# Buttons.net
KiCad netlist of a schematic drawn in Altium Designer
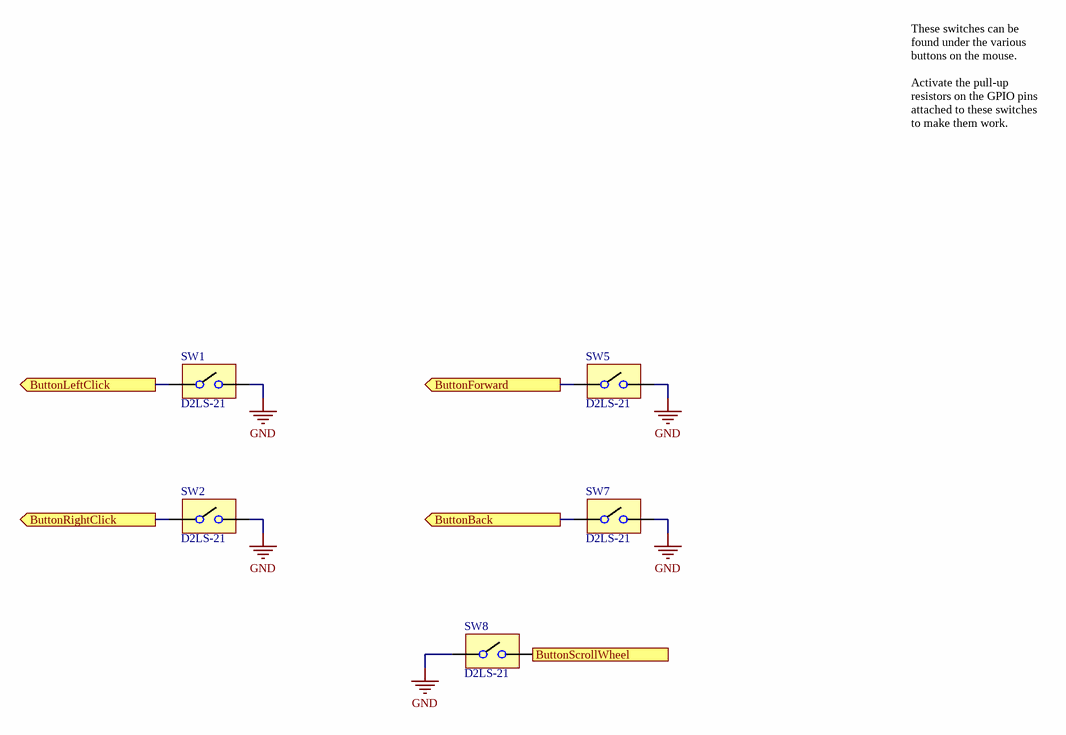
[diagram p0: Buttons.SchDoc]

(export (version "E")
  (design (tool "Eeschema 10.0.6"))
  (components
    (comp (ref "SW1")
      (value "D2LS-21")
      (footprint "D2LS-21")
      (description "Compact Surface-mounting Switch for long durability")
      (libsource (lib "Switches") (part "D2LS-21"))
    )
    (comp (ref "SW2")
      (value "D2LS-21")
      (footprint "D2LS-21")
      (description "Compact Surface-mounting Switch for long durability")
      (libsource (lib "Switches") (part "D2LS-21"))
    )
    (comp (ref "SW5")
      (value "D2LS-21")
      (footprint "D2LS-21")
      (description "Compact Surface-mounting Switch for long durability")
      (libsource (lib "Switches") (part "D2LS-21"))
    )
    (comp (ref "SW7")
      (value "D2LS-21")
      (footprint "D2LS-21")
      (description "Compact Surface-mounting Switch for long durability")
      (libsource (lib "Switches") (part "D2LS-21"))
    )
    (comp (ref "SW8")
      (value "D2LS-21")
      (footprint "D2LS-21")
      (description "Compact Surface-mounting Switch for long durability")
      (libsource (lib "Switches") (part "D2LS-21"))
    )
  )
  (nets
    (net (code "1") (name "/ButtonBack") (class "Default")
      (node (ref "SW7") (pin "A") (pinfunction "A_A") (pintype "passive"))
    )
    (net (code "2") (name "/ButtonForward") (class "Default")
      (node (ref "SW5") (pin "A") (pinfunction "A_A") (pintype "passive"))
    )
    (net (code "3") (name "/ButtonLeftClick") (class "Default")
      (node (ref "SW1") (pin "A") (pinfunction "A_A") (pintype "passive"))
    )
    (net (code "4") (name "/ButtonRightClick") (class "Default")
      (node (ref "SW2") (pin "A") (pinfunction "A_A") (pintype "passive"))
    )
    (net (code "5") (name "/ButtonScrollWheel") (class "Default")
      (node (ref "SW8") (pin "B") (pinfunction "B_B") (pintype "passive"))
    )
    (net (code "6") (name "GND") (class "Default")
      (node (ref "SW1") (pin "B") (pinfunction "B_B") (pintype "passive"))
      (node (ref "SW2") (pin "B") (pinfunction "B_B") (pintype "passive"))
      (node (ref "SW5") (pin "B") (pinfunction "B_B") (pintype "passive"))
      (node (ref "SW7") (pin "B") (pinfunction "B_B") (pintype "passive"))
      (node (ref "SW8") (pin "A") (pinfunction "A_A") (pintype "passive"))
    )
  )
)
